# PI2GENESIS-HUB_V20170403.net
KiCad netlist of a schematic drawn in EAGLE
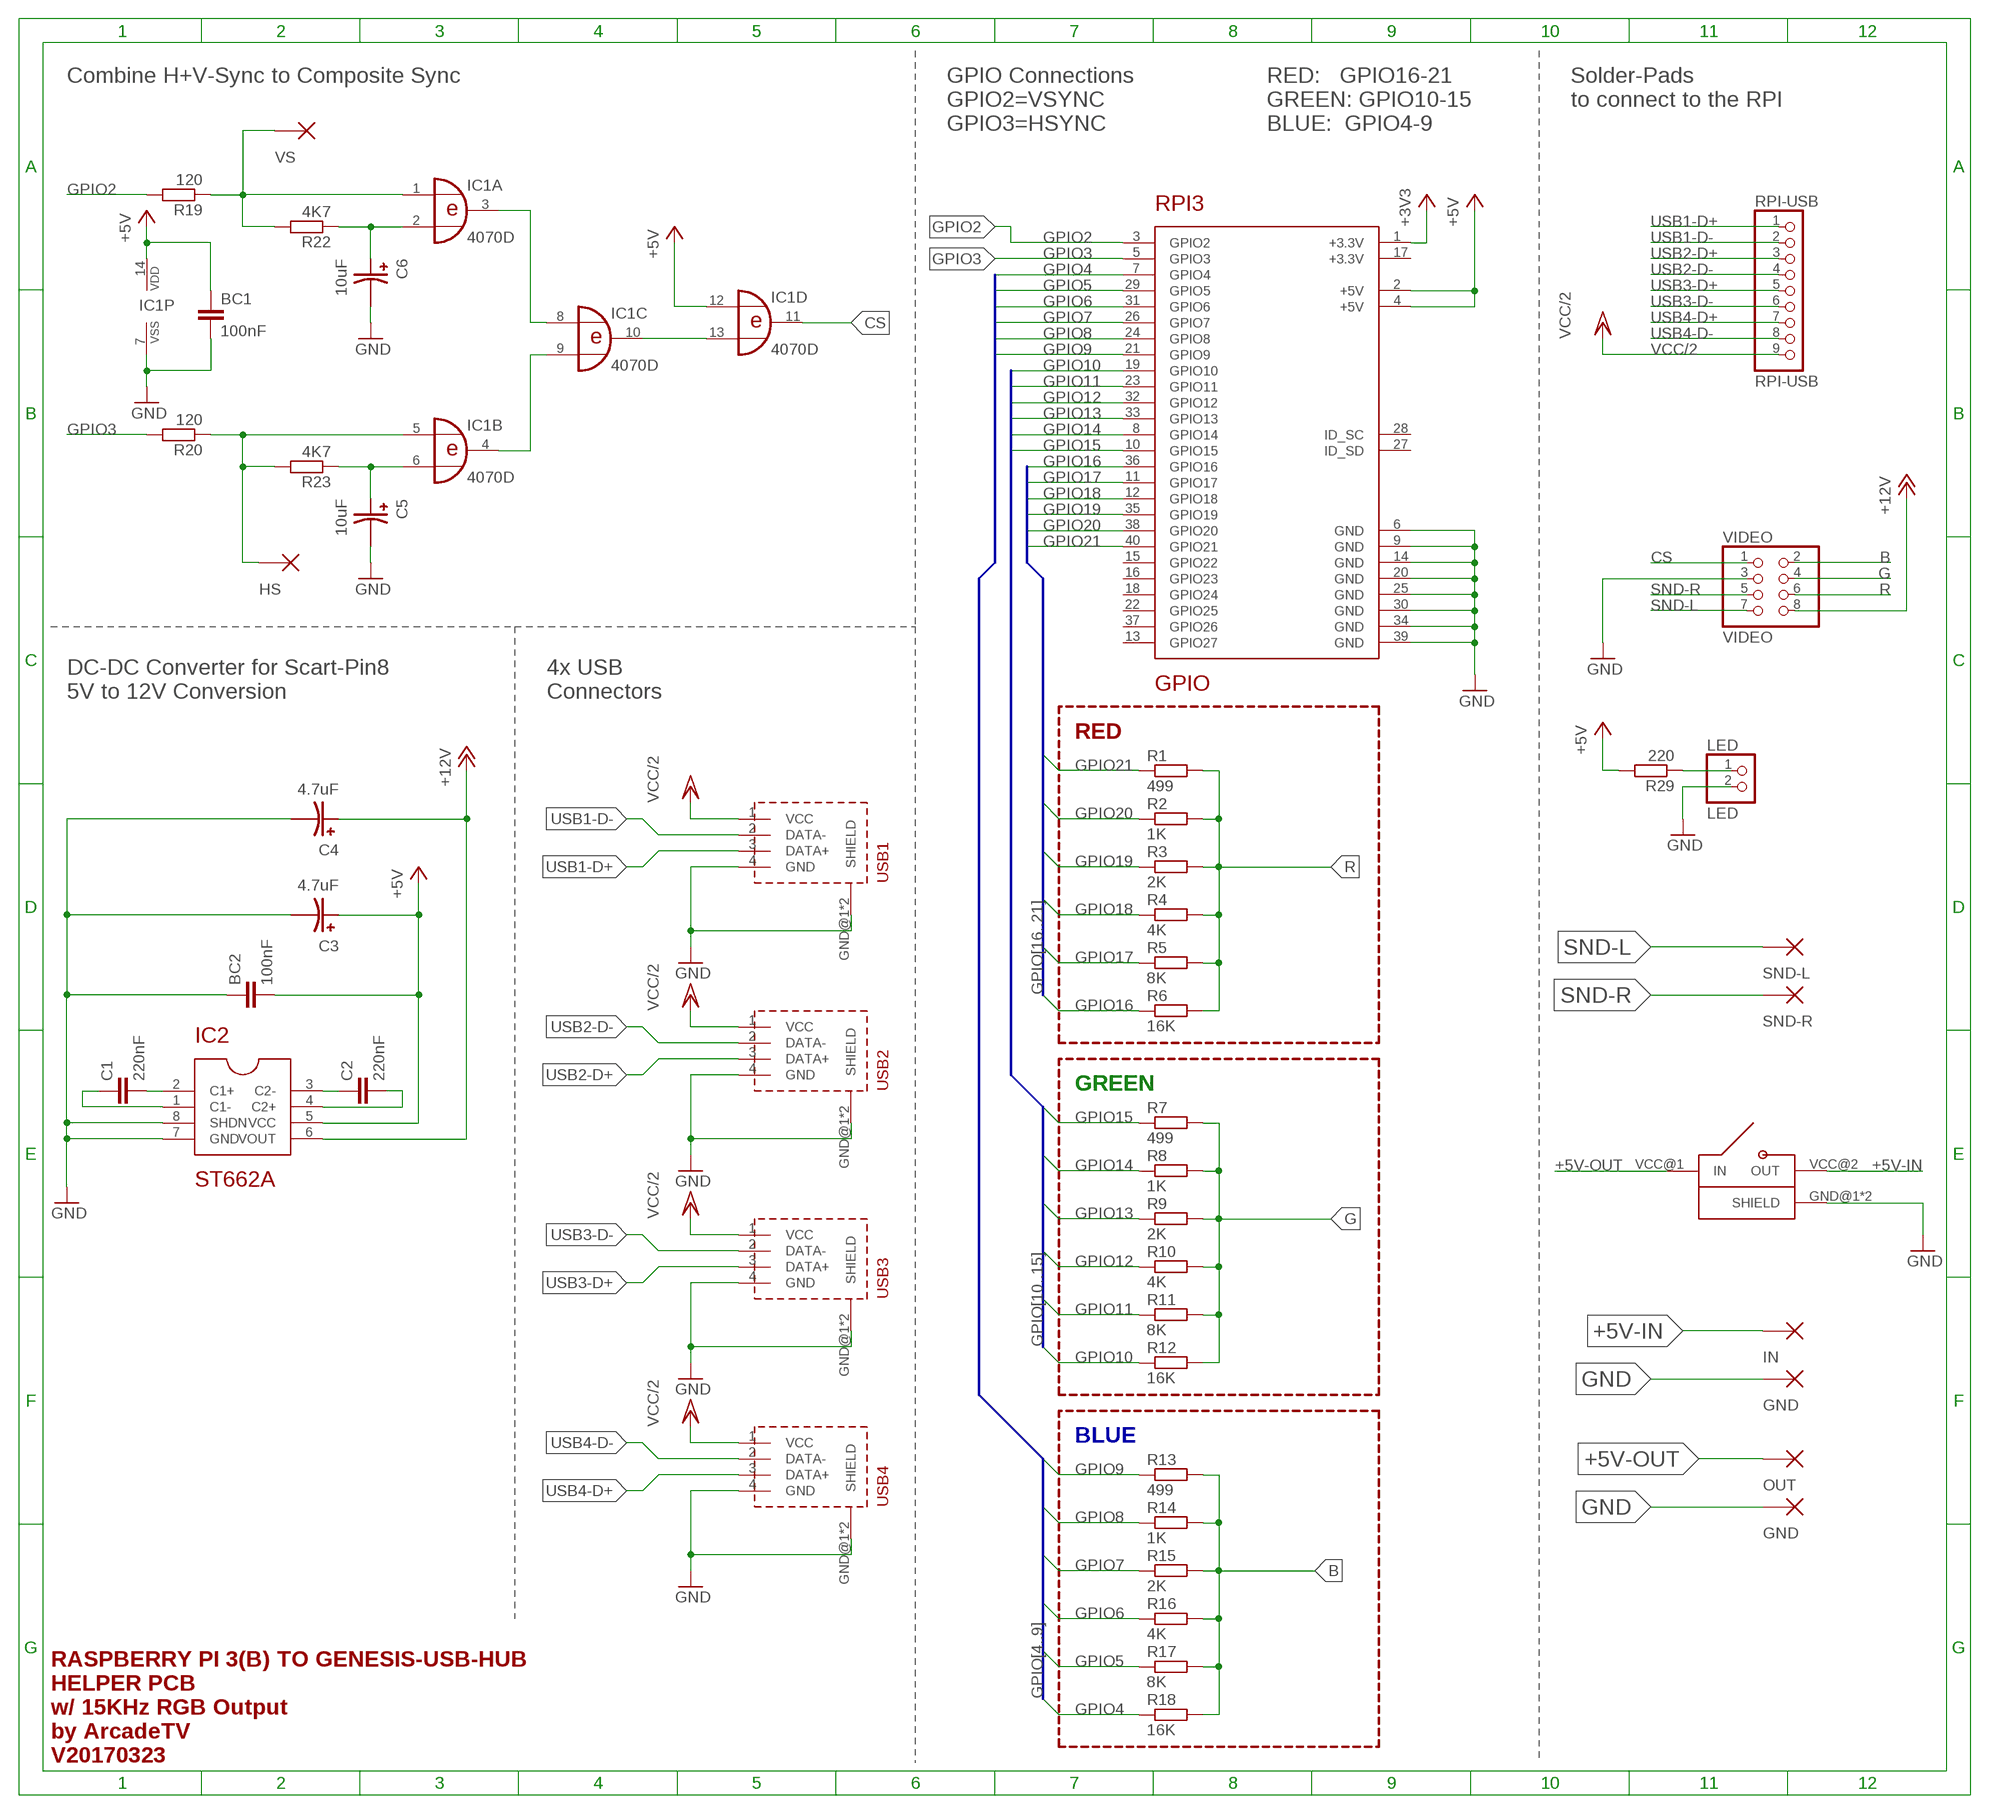
[diagram p0: schematic, sheet 1]

(export (version "E")
  (design (tool "Eeschema 10.0.6"))
  (components
    (comp (ref "BC1")
      (value "100nF")
      (footprint "eagle-import:Z0805")
      (libsource (lib "eagle-import") (part "C0805"))
    )
    (comp (ref "BC2")
      (value "100nF")
      (footprint "eagle-import:Z0805")
      (libsource (lib "eagle-import") (part "C0805"))
    )
    (comp (ref "C1")
      (value "220nF")
      (footprint "eagle-import:Z0805")
      (libsource (lib "eagle-import") (part "C0805"))
    )
    (comp (ref "C2")
      (value "220nF")
      (footprint "eagle-import:Z0805")
      (libsource (lib "eagle-import") (part "C0805"))
    )
    (comp (ref "C3")
      (value "4.7uF")
      (footprint "eagle-import:EEEFPJ101UAR_PANASONIC_VFP-SERIES")
      (libsource (lib "eagle-import") (part "EEEFPJ101UAR_PANASONIC_VFP-SERIES"))
    )
    (comp (ref "C4")
      (value "4.7uF")
      (footprint "eagle-import:EEEFPJ101UAR_PANASONIC_VFP-SERIES")
      (libsource (lib "eagle-import") (part "EEEFPJ101UAR_PANASONIC_VFP-SERIES"))
    )
    (comp (ref "C5")
      (value "10uF")
      (footprint "eagle-import:EEEFPJ101UAR_PANASONIC_VFP-SERIES")
      (libsource (lib "eagle-import") (part "EEEFPJ101UAR_PANASONIC_VFP-SERIES"))
    )
    (comp (ref "C6")
      (value "10uF")
      (footprint "eagle-import:EEEFPJ101UAR_PANASONIC_VFP-SERIES")
      (libsource (lib "eagle-import") (part "EEEFPJ101UAR_PANASONIC_VFP-SERIES"))
    )
    (comp (ref "IC1")
      (value "4070D")
      (footprint "eagle-import:SO14")
      (libsource (lib "eagle-import") (part "4070D"))
    )
    (comp (ref "IC2")
      (value "ST662A")
      (footprint "eagle-import:SO-8")
      (libsource (lib "eagle-import") (part "ST662A"))
    )
    (comp (ref "LED")
      (value "LED")
      (footprint "eagle-import:1X02")
      (libsource (lib "eagle-import") (part "PINHD-1X2"))
    )
    (comp (ref "PAD1")
      (value "HS")
      (footprint "eagle-import:PADS")
      (libsource (lib "eagle-import") (part "PAD"))
    )
    (comp (ref "PAD2")
      (value "VS")
      (footprint "eagle-import:PADS")
      (libsource (lib "eagle-import") (part "PAD"))
    )
    (comp (ref "R1")
      (value "499")
      (footprint "eagle-import:Z0805")
      (libsource (lib "eagle-import") (part "R0805"))
    )
    (comp (ref "R2")
      (value "1K")
      (footprint "eagle-import:Z0805")
      (libsource (lib "eagle-import") (part "R0805"))
    )
    (comp (ref "R3")
      (value "2K")
      (footprint "eagle-import:Z0805")
      (libsource (lib "eagle-import") (part "R0805"))
    )
    (comp (ref "R4")
      (value "4K")
      (footprint "eagle-import:Z0805")
      (libsource (lib "eagle-import") (part "R0805"))
    )
    (comp (ref "R5")
      (value "8K")
      (footprint "eagle-import:Z0805")
      (libsource (lib "eagle-import") (part "R0805"))
    )
    (comp (ref "R6")
      (value "16K")
      (footprint "eagle-import:Z0805")
      (libsource (lib "eagle-import") (part "R0805"))
    )
    (comp (ref "R7")
      (value "499")
      (footprint "eagle-import:Z0805")
      (libsource (lib "eagle-import") (part "R0805"))
    )
    (comp (ref "R8")
      (value "1K")
      (footprint "eagle-import:Z0805")
      (libsource (lib "eagle-import") (part "R0805"))
    )
    (comp (ref "R9")
      (value "2K")
      (footprint "eagle-import:Z0805")
      (libsource (lib "eagle-import") (part "R0805"))
    )
    (comp (ref "R10")
      (value "4K")
      (footprint "eagle-import:Z0805")
      (libsource (lib "eagle-import") (part "R0805"))
    )
    (comp (ref "R11")
      (value "8K")
      (footprint "eagle-import:Z0805")
      (libsource (lib "eagle-import") (part "R0805"))
    )
    (comp (ref "R12")
      (value "16K")
      (footprint "eagle-import:Z0805")
      (libsource (lib "eagle-import") (part "R0805"))
    )
    (comp (ref "R13")
      (value "499")
      (footprint "eagle-import:Z0805")
      (libsource (lib "eagle-import") (part "R0805"))
    )
    (comp (ref "R14")
      (value "1K")
      (footprint "eagle-import:Z0805")
      (libsource (lib "eagle-import") (part "R0805"))
    )
    (comp (ref "R15")
      (value "2K")
      (footprint "eagle-import:Z0805")
      (libsource (lib "eagle-import") (part "R0805"))
    )
    (comp (ref "R16")
      (value "4K")
      (footprint "eagle-import:Z0805")
      (libsource (lib "eagle-import") (part "R0805"))
    )
    (comp (ref "R17")
      (value "8K")
      (footprint "eagle-import:Z0805")
      (libsource (lib "eagle-import") (part "R0805"))
    )
    (comp (ref "R18")
      (value "16K")
      (footprint "eagle-import:Z0805")
      (libsource (lib "eagle-import") (part "R0805"))
    )
    (comp (ref "R19")
      (value "120")
      (footprint "eagle-import:Z0805")
      (libsource (lib "eagle-import") (part "R0805"))
    )
    (comp (ref "R20")
      (value "120")
      (footprint "eagle-import:Z0805")
      (libsource (lib "eagle-import") (part "R0805"))
    )
    (comp (ref "R22")
      (value "4K7")
      (footprint "eagle-import:Z0805")
      (libsource (lib "eagle-import") (part "R0805"))
    )
    (comp (ref "R23")
      (value "4K7")
      (footprint "eagle-import:Z0805")
      (libsource (lib "eagle-import") (part "R0805"))
    )
    (comp (ref "R29")
      (value "220")
      (footprint "eagle-import:Z0805")
      (libsource (lib "eagle-import") (part "R0805"))
    )
    (comp (ref "RPI-USB")
      (value "RPI-USB")
      (footprint "eagle-import:1X09")
      (libsource (lib "eagle-import") (part "PINHD-1X9"))
    )
    (comp (ref "RPI3")
      (value "GPIO")
      (footprint "eagle-import:RPI3-GPIO")
      (libsource (lib "eagle-import") (part "RPI3-GPIOSTANDARD"))
    )
    (comp (ref "U$1")
      (value "OUT")
      (footprint "eagle-import:PADS")
      (libsource (lib "eagle-import") (part "PAD"))
    )
    (comp (ref "U$2")
      (value "SND-L")
      (footprint "eagle-import:PADS")
      (libsource (lib "eagle-import") (part "PAD"))
    )
    (comp (ref "U$3")
      (value "SND-R")
      (footprint "eagle-import:PADS")
      (libsource (lib "eagle-import") (part "PAD"))
    )
    (comp (ref "U$4")
      (value "ALPS-SSSU011700")
      (footprint "eagle-import:ALPS-SSSU011700")
      (libsource (lib "eagle-import") (part "ALPS-SSSU011700"))
    )
    (comp (ref "U$5")
      (value "IN")
      (footprint "eagle-import:PADS")
      (libsource (lib "eagle-import") (part "PAD"))
    )
    (comp (ref "U$6")
      (value "GND")
      (footprint "eagle-import:PADS")
      (libsource (lib "eagle-import") (part "PAD"))
    )
    (comp (ref "U$7")
      (value "GND")
      (footprint "eagle-import:PADS")
      (libsource (lib "eagle-import") (part "PAD"))
    )
    (comp (ref "USB1")
      (value "USB-GENESIS-HUB")
      (footprint "eagle-import:USB-GENESIS-HUB")
      (libsource (lib "eagle-import") (part "USB-GENESIS-HUB"))
    )
    (comp (ref "USB2")
      (value "USB-GENESIS-HUB")
      (footprint "eagle-import:USB-GENESIS-HUB")
      (libsource (lib "eagle-import") (part "USB-GENESIS-HUB"))
    )
    (comp (ref "USB3")
      (value "USB-GENESIS-HUB")
      (footprint "eagle-import:USB-GENESIS-HUB")
      (libsource (lib "eagle-import") (part "USB-GENESIS-HUB"))
    )
    (comp (ref "USB4")
      (value "USB-GENESIS-HUB")
      (footprint "eagle-import:USB-GENESIS-HUB")
      (libsource (lib "eagle-import") (part "USB-GENESIS-HUB"))
    )
    (comp (ref "VIDEO")
      (value "VIDEO")
      (footprint "eagle-import:2X04")
      (libsource (lib "eagle-import") (part "PINHD-2X4"))
    )
  )
  (nets
    (net (code "1") (name "+3V3") (class "Default")
      (node (ref "RPI3") (pin "1") (pinfunction "+3.3V_1") (pintype "bidirectional"))
    )
    (net (code "2") (name "+5V") (class "Default")
      (node (ref "BC1") (pin "1") (pinfunction "1_1") (pintype "passive"))
      (node (ref "BC2") (pin "2") (pinfunction "2_2") (pintype "passive"))
      (node (ref "C3") (pin "PLUS") (pinfunction "+_PLUS") (pintype "bidirectional"))
      (node (ref "IC1") (pin "12") (pinfunction "I0_12") (pintype "input"))
      (node (ref "IC1") (pin "14") (pinfunction "VDD_14") (pintype "power_in"))
      (node (ref "IC2") (pin "5") (pinfunction "VCC_5") (pintype "bidirectional"))
      (node (ref "R29") (pin "2") (pinfunction "2_2") (pintype "passive"))
      (node (ref "RPI3") (pin "2") (pinfunction "+5V_2") (pintype "bidirectional"))
      (node (ref "RPI3") (pin "4") (pinfunction "+5V_4") (pintype "bidirectional"))
    )
    (net (code "3") (name "+5V-IN") (class "Default")
      (node (ref "U$4") (pin "VCC@2") (pinfunction "OUT_VCC@2") (pintype "bidirectional"))
      (node (ref "U$5") (pin "P$1") (pinfunction "P$1_P$1") (pintype "bidirectional"))
    )
    (net (code "4") (name "+5V-OUT") (class "Default")
      (node (ref "U$1") (pin "P$1") (pinfunction "P$1_P$1") (pintype "bidirectional"))
      (node (ref "U$4") (pin "VCC@1") (pinfunction "IN_VCC@1") (pintype "bidirectional"))
    )
    (net (code "5") (name "+12V") (class "Default")
      (node (ref "C4") (pin "PLUS") (pinfunction "+_PLUS") (pintype "bidirectional"))
      (node (ref "IC2") (pin "6") (pinfunction "VOUT_6") (pintype "bidirectional"))
      (node (ref "VIDEO") (pin "8") (pinfunction "8_8") (pintype "passive"))
    )
    (net (code "6") (name "/GPIO4") (class "Default")
      (node (ref "R18") (pin "1") (pinfunction "1_1") (pintype "passive"))
      (node (ref "RPI3") (pin "7") (pinfunction "GPIO4_7") (pintype "bidirectional"))
    )
    (net (code "7") (name "/GPIO5") (class "Default")
      (node (ref "R17") (pin "1") (pinfunction "1_1") (pintype "passive"))
      (node (ref "RPI3") (pin "29") (pinfunction "GPIO5_29") (pintype "bidirectional"))
    )
    (net (code "8") (name "/GPIO6") (class "Default")
      (node (ref "R16") (pin "1") (pinfunction "1_1") (pintype "passive"))
      (node (ref "RPI3") (pin "31") (pinfunction "GPIO6_31") (pintype "bidirectional"))
    )
    (net (code "9") (name "/GPIO7") (class "Default")
      (node (ref "R15") (pin "1") (pinfunction "1_1") (pintype "passive"))
      (node (ref "RPI3") (pin "26") (pinfunction "GPIO7_26") (pintype "bidirectional"))
    )
    (net (code "10") (name "/GPIO8") (class "Default")
      (node (ref "R14") (pin "1") (pinfunction "1_1") (pintype "passive"))
      (node (ref "RPI3") (pin "24") (pinfunction "GPIO8_24") (pintype "bidirectional"))
    )
    (net (code "11") (name "/GPIO9") (class "Default")
      (node (ref "R13") (pin "1") (pinfunction "1_1") (pintype "passive"))
      (node (ref "RPI3") (pin "21") (pinfunction "GPIO9_21") (pintype "bidirectional"))
    )
    (net (code "12") (name "/GPIO10") (class "Default")
      (node (ref "R12") (pin "1") (pinfunction "1_1") (pintype "passive"))
      (node (ref "RPI3") (pin "19") (pinfunction "GPIO10_19") (pintype "bidirectional"))
    )
    (net (code "13") (name "/GPIO11") (class "Default")
      (node (ref "R11") (pin "1") (pinfunction "1_1") (pintype "passive"))
      (node (ref "RPI3") (pin "23") (pinfunction "GPIO11_23") (pintype "bidirectional"))
    )
    (net (code "14") (name "/GPIO12") (class "Default")
      (node (ref "R10") (pin "1") (pinfunction "1_1") (pintype "passive"))
      (node (ref "RPI3") (pin "32") (pinfunction "GPIO12_32") (pintype "bidirectional"))
    )
    (net (code "15") (name "/GPIO13") (class "Default")
      (node (ref "R9") (pin "1") (pinfunction "1_1") (pintype "passive"))
      (node (ref "RPI3") (pin "33") (pinfunction "GPIO13_33") (pintype "bidirectional"))
    )
    (net (code "16") (name "/GPIO14") (class "Default")
      (node (ref "R8") (pin "1") (pinfunction "1_1") (pintype "passive"))
      (node (ref "RPI3") (pin "8") (pinfunction "GPIO14_8") (pintype "bidirectional"))
    )
    (net (code "17") (name "/GPIO15") (class "Default")
      (node (ref "R7") (pin "1") (pinfunction "1_1") (pintype "passive"))
      (node (ref "RPI3") (pin "10") (pinfunction "GPIO15_10") (pintype "bidirectional"))
    )
    (net (code "18") (name "/GPIO16") (class "Default")
      (node (ref "R6") (pin "1") (pinfunction "1_1") (pintype "passive"))
      (node (ref "RPI3") (pin "36") (pinfunction "GPIO16_36") (pintype "bidirectional"))
    )
    (net (code "19") (name "/GPIO17") (class "Default")
      (node (ref "R5") (pin "1") (pinfunction "1_1") (pintype "passive"))
      (node (ref "RPI3") (pin "11") (pinfunction "GPIO17_11") (pintype "bidirectional"))
    )
    (net (code "20") (name "/GPIO18") (class "Default")
      (node (ref "R4") (pin "1") (pinfunction "1_1") (pintype "passive"))
      (node (ref "RPI3") (pin "12") (pinfunction "GPIO18_12") (pintype "bidirectional"))
    )
    (net (code "21") (name "/GPIO19") (class "Default")
      (node (ref "R3") (pin "1") (pinfunction "1_1") (pintype "passive"))
      (node (ref "RPI3") (pin "35") (pinfunction "GPIO19_35") (pintype "bidirectional"))
    )
    (net (code "22") (name "/GPIO20") (class "Default")
      (node (ref "R2") (pin "1") (pinfunction "1_1") (pintype "passive"))
      (node (ref "RPI3") (pin "38") (pinfunction "GPIO20_38") (pintype "bidirectional"))
    )
    (net (code "23") (name "/GPIO21") (class "Default")
      (node (ref "R1") (pin "1") (pinfunction "1_1") (pintype "passive"))
      (node (ref "RPI3") (pin "40") (pinfunction "GPIO21_40") (pintype "bidirectional"))
    )
    (net (code "24") (name "B") (class "Default")
      (node (ref "R13") (pin "2") (pinfunction "2_2") (pintype "passive"))
      (node (ref "R14") (pin "2") (pinfunction "2_2") (pintype "passive"))
      (node (ref "R15") (pin "2") (pinfunction "2_2") (pintype "passive"))
      (node (ref "R16") (pin "2") (pinfunction "2_2") (pintype "passive"))
      (node (ref "R17") (pin "2") (pinfunction "2_2") (pintype "passive"))
      (node (ref "R18") (pin "2") (pinfunction "2_2") (pintype "passive"))
      (node (ref "VIDEO") (pin "2") (pinfunction "2_2") (pintype "passive"))
    )
    (net (code "25") (name "CS") (class "Default")
      (node (ref "IC1") (pin "11") (pinfunction "O_11") (pintype "output"))
      (node (ref "VIDEO") (pin "1") (pinfunction "1_1") (pintype "passive"))
    )
    (net (code "26") (name "G") (class "Default")
      (node (ref "R10") (pin "2") (pinfunction "2_2") (pintype "passive"))
      (node (ref "R11") (pin "2") (pinfunction "2_2") (pintype "passive"))
      (node (ref "R12") (pin "2") (pinfunction "2_2") (pintype "passive"))
      (node (ref "R7") (pin "2") (pinfunction "2_2") (pintype "passive"))
      (node (ref "R8") (pin "2") (pinfunction "2_2") (pintype "passive"))
      (node (ref "R9") (pin "2") (pinfunction "2_2") (pintype "passive"))
      (node (ref "VIDEO") (pin "4") (pinfunction "4_4") (pintype "passive"))
    )
    (net (code "27") (name "GND") (class "Default")
      (node (ref "BC1") (pin "2") (pinfunction "2_2") (pintype "passive"))
      (node (ref "BC2") (pin "1") (pinfunction "1_1") (pintype "passive"))
      (node (ref "C3") (pin "MINUS") (pinfunction "-_MINUS") (pintype "bidirectional"))
      (node (ref "C4") (pin "MINUS") (pinfunction "-_MINUS") (pintype "bidirectional"))
      (node (ref "C5") (pin "MINUS") (pinfunction "-_MINUS") (pintype "bidirectional"))
      (node (ref "C6") (pin "MINUS") (pinfunction "-_MINUS") (pintype "bidirectional"))
      (node (ref "IC1") (pin "7") (pinfunction "VSS_7") (pintype "power_in"))
      (node (ref "IC2") (pin "7") (pinfunction "GND_7") (pintype "bidirectional"))
      (node (ref "IC2") (pin "8") (pinfunction "SHDN_8") (pintype "bidirectional"))
      (node (ref "LED") (pin "2") (pinfunction "2_2") (pintype "passive"))
      (node (ref "RPI3") (pin "14") (pinfunction "GND_14") (pintype "bidirectional"))
      (node (ref "RPI3") (pin "20") (pinfunction "GND_20") (pintype "bidirectional"))
      (node (ref "RPI3") (pin "25") (pinfunction "GND_25") (pintype "bidirectional"))
      (node (ref "RPI3") (pin "30") (pinfunction "GND_30") (pintype "bidirectional"))
      (node (ref "RPI3") (pin "34") (pinfunction "GND_34") (pintype "bidirectional"))
      (node (ref "RPI3") (pin "39") (pinfunction "GND_39") (pintype "bidirectional"))
      (node (ref "RPI3") (pin "6") (pinfunction "GND_6") (pintype "bidirectional"))
      (node (ref "RPI3") (pin "9") (pinfunction "GND_9") (pintype "bidirectional"))
      (node (ref "U$4") (pin "GND@1") (pinfunction "SHIELD_GND@1") (pintype "bidirectional"))
      (node (ref "U$4") (pin "GND@2") (pinfunction "SHIELD_GND@2") (pintype "bidirectional"))
      (node (ref "U$6") (pin "P$1") (pinfunction "P$1_P$1") (pintype "bidirectional"))
      (node (ref "U$7") (pin "P$1") (pinfunction "P$1_P$1") (pintype "bidirectional"))
      (node (ref "USB1") (pin "4") (pinfunction "GND_4") (pintype "bidirectional"))
      (node (ref "USB1") (pin "GND@1") (pinfunction "SHIELD_GND@1") (pintype "bidirectional"))
      (node (ref "USB1") (pin "GND@2") (pinfunction "SHIELD_GND@2") (pintype "bidirectional"))
      (node (ref "USB2") (pin "4") (pinfunction "GND_4") (pintype "bidirectional"))
      (node (ref "USB2") (pin "GND@1") (pinfunction "SHIELD_GND@1") (pintype "bidirectional"))
      (node (ref "USB2") (pin "GND@2") (pinfunction "SHIELD_GND@2") (pintype "bidirectional"))
      (node (ref "USB3") (pin "4") (pinfunction "GND_4") (pintype "bidirectional"))
      (node (ref "USB3") (pin "GND@1") (pinfunction "SHIELD_GND@1") (pintype "bidirectional"))
      (node (ref "USB3") (pin "GND@2") (pinfunction "SHIELD_GND@2") (pintype "bidirectional"))
      (node (ref "USB4") (pin "4") (pinfunction "GND_4") (pintype "bidirectional"))
      (node (ref "USB4") (pin "GND@1") (pinfunction "SHIELD_GND@1") (pintype "bidirectional"))
      (node (ref "USB4") (pin "GND@2") (pinfunction "SHIELD_GND@2") (pintype "bidirectional"))
      (node (ref "VIDEO") (pin "3") (pinfunction "3_3") (pintype "passive"))
    )
    (net (code "28") (name "GPIO2") (class "Default")
      (node (ref "R19") (pin "2") (pinfunction "2_2") (pintype "passive"))
      (node (ref "RPI3") (pin "3") (pinfunction "GPIO2_3") (pintype "bidirectional"))
    )
    (net (code "29") (name "GPIO3") (class "Default")
      (node (ref "R20") (pin "2") (pinfunction "2_2") (pintype "passive"))
      (node (ref "RPI3") (pin "5") (pinfunction "GPIO3_5") (pintype "bidirectional"))
    )
    (net (code "30") (name "Net-(C5-+)") (class "Default")
      (node (ref "C5") (pin "PLUS") (pinfunction "+_PLUS") (pintype "bidirectional"))
      (node (ref "IC1") (pin "6") (pinfunction "I1_6") (pintype "input"))
      (node (ref "R23") (pin "1") (pinfunction "1_1") (pintype "passive"))
    )
    (net (code "31") (name "Net-(C6-+)") (class "Default")
      (node (ref "C6") (pin "PLUS") (pinfunction "+_PLUS") (pintype "bidirectional"))
      (node (ref "IC1") (pin "2") (pinfunction "I1_2") (pintype "input"))
      (node (ref "R22") (pin "1") (pinfunction "1_1") (pintype "passive"))
    )
    (net (code "32") (name "Net-(IC1A-I0)") (class "Default")
      (node (ref "IC1") (pin "1") (pinfunction "I0_1") (pintype "input"))
      (node (ref "PAD2") (pin "P$1") (pinfunction "P$1_P$1") (pintype "bidirectional"))
      (node (ref "R19") (pin "1") (pinfunction "1_1") (pintype "passive"))
      (node (ref "R22") (pin "2") (pinfunction "2_2") (pintype "passive"))
    )
    (net (code "33") (name "Net-(IC1A-O)") (class "Default")
      (node (ref "IC1") (pin "3") (pinfunction "O_3") (pintype "output"))
      (node (ref "IC1") (pin "8") (pinfunction "I0_8") (pintype "input"))
    )
    (net (code "34") (name "Net-(IC1B-I0)") (class "Default")
      (node (ref "IC1") (pin "5") (pinfunction "I0_5") (pintype "input"))
      (node (ref "PAD1") (pin "P$1") (pinfunction "P$1_P$1") (pintype "bidirectional"))
      (node (ref "R20") (pin "1") (pinfunction "1_1") (pintype "passive"))
      (node (ref "R23") (pin "2") (pinfunction "2_2") (pintype "passive"))
    )
    (net (code "35") (name "Net-(IC1B-O)") (class "Default")
      (node (ref "IC1") (pin "4") (pinfunction "O_4") (pintype "output"))
      (node (ref "IC1") (pin "9") (pinfunction "I1_9") (pintype "input"))
    )
    (net (code "36") (name "Net-(IC1C-O)") (class "Default")
      (node (ref "IC1") (pin "10") (pinfunction "O_10") (pintype "output"))
      (node (ref "IC1") (pin "13") (pinfunction "I1_13") (pintype "input"))
    )
    (net (code "37") (name "Net-(IC2-C1+)") (class "Default")
      (node (ref "C1") (pin "2") (pinfunction "2_2") (pintype "passive"))
      (node (ref "IC2") (pin "2") (pinfunction "C1+_2") (pintype "bidirectional"))
    )
    (net (code "38") (name "Net-(IC2-C1-)") (class "Default")
      (node (ref "C1") (pin "1") (pinfunction "1_1") (pintype "passive"))
      (node (ref "IC2") (pin "1") (pinfunction "C1-_1") (pintype "bidirectional"))
    )
    (net (code "39") (name "Net-(IC2-C2+)") (class "Default")
      (node (ref "C2") (pin "2") (pinfunction "2_2") (pintype "passive"))
      (node (ref "IC2") (pin "4") (pinfunction "C2+_4") (pintype "bidirectional"))
    )
    (net (code "40") (name "Net-(IC2-C2-)") (class "Default")
      (node (ref "C2") (pin "1") (pinfunction "1_1") (pintype "passive"))
      (node (ref "IC2") (pin "3") (pinfunction "C2-_3") (pintype "bidirectional"))
    )
    (net (code "41") (name "Net-(LED-Pad1)") (class "Default")
      (node (ref "LED") (pin "1") (pinfunction "1_1") (pintype "passive"))
      (node (ref "R29") (pin "1") (pinfunction "1_1") (pintype "passive"))
    )
    (net (code "42") (name "R") (class "Default")
      (node (ref "R1") (pin "2") (pinfunction "2_2") (pintype "passive"))
      (node (ref "R2") (pin "2") (pinfunction "2_2") (pintype "passive"))
      (node (ref "R3") (pin "2") (pinfunction "2_2") (pintype "passive"))
      (node (ref "R4") (pin "2") (pinfunction "2_2") (pintype "passive"))
      (node (ref "R5") (pin "2") (pinfunction "2_2") (pintype "passive"))
      (node (ref "R6") (pin "2") (pinfunction "2_2") (pintype "passive"))
      (node (ref "VIDEO") (pin "6") (pinfunction "6_6") (pintype "passive"))
    )
    (net (code "43") (name "SND-L") (class "Default")
      (node (ref "U$2") (pin "P$1") (pinfunction "P$1_P$1") (pintype "bidirectional"))
      (node (ref "VIDEO") (pin "7") (pinfunction "7_7") (pintype "passive"))
    )
    (net (code "44") (name "SND-R") (class "Default")
      (node (ref "U$3") (pin "P$1") (pinfunction "P$1_P$1") (pintype "bidirectional"))
      (node (ref "VIDEO") (pin "5") (pinfunction "5_5") (pintype "passive"))
    )
    (net (code "45") (name "USB1-D+") (class "Default")
      (node (ref "RPI-USB") (pin "1") (pinfunction "1_1") (pintype "passive"))
      (node (ref "USB1") (pin "3") (pinfunction "DATA+_3") (pintype "bidirectional"))
    )
    (net (code "46") (name "USB1-D-") (class "Default")
      (node (ref "RPI-USB") (pin "2") (pinfunction "2_2") (pintype "passive"))
      (node (ref "USB1") (pin "2") (pinfunction "DATA-_2") (pintype "bidirectional"))
    )
    (net (code "47") (name "USB2-D+") (class "Default")
      (node (ref "RPI-USB") (pin "3") (pinfunction "3_3") (pintype "passive"))
      (node (ref "USB2") (pin "3") (pinfunction "DATA+_3") (pintype "bidirectional"))
    )
    (net (code "48") (name "USB2-D-") (class "Default")
      (node (ref "RPI-USB") (pin "4") (pinfunction "4_4") (pintype "passive"))
      (node (ref "USB2") (pin "2") (pinfunction "DATA-_2") (pintype "bidirectional"))
    )
    (net (code "49") (name "USB3-D+") (class "Default")
      (node (ref "RPI-USB") (pin "5") (pinfunction "5_5") (pintype "passive"))
      (node (ref "USB3") (pin "3") (pinfunction "DATA+_3") (pintype "bidirectional"))
    )
    (net (code "50") (name "USB3-D-") (class "Default")
      (node (ref "RPI-USB") (pin "6") (pinfunction "6_6") (pintype "passive"))
      (node (ref "USB3") (pin "2") (pinfunction "DATA-_2") (pintype "bidirectional"))
    )
    (net (code "51") (name "USB4-D+") (class "Default")
      (node (ref "RPI-USB") (pin "7") (pinfunction "7_7") (pintype "passive"))
      (node (ref "USB4") (pin "3") (pinfunction "DATA+_3") (pintype "bidirectional"))
    )
    (net (code "52") (name "USB4-D-") (class "Default")
      (node (ref "RPI-USB") (pin "8") (pinfunction "8_8") (pintype "passive"))
      (node (ref "USB4") (pin "2") (pinfunction "DATA-_2") (pintype "bidirectional"))
    )
    (net (code "53") (name "VCC{slash}2") (class "Default")
      (node (ref "RPI-USB") (pin "9") (pinfunction "9_9") (pintype "passive"))
      (node (ref "USB1") (pin "1") (pinfunction "VCC_1") (pintype "bidirectional"))
      (node (ref "USB2") (pin "1") (pinfunction "VCC_1") (pintype "bidirectional"))
      (node (ref "USB3") (pin "1") (pinfunction "VCC_1") (pintype "bidirectional"))
      (node (ref "USB4") (pin "1") (pinfunction "VCC_1") (pintype "bidirectional"))
    )
    (net (code "54") (name "unconnected-(RPI3-+3.3V-Pad17)") (class "Default")
      (node (ref "RPI3") (pin "17") (pinfunction "+3.3V_17") (pintype "bidirectional"))
    )
    (net (code "55") (name "unconnected-(RPI3-GPIO22-Pad15)") (class "Default")
      (node (ref "RPI3") (pin "15") (pinfunction "GPIO22_15") (pintype "bidirectional"))
    )
    (net (code "56") (name "unconnected-(RPI3-GPIO23-Pad16)") (class "Default")
      (node (ref "RPI3") (pin "16") (pinfunction "GPIO23_16") (pintype "bidirectional"))
    )
    (net (code "57") (name "unconnected-(RPI3-GPIO24-Pad18)") (class "Default")
      (node (ref "RPI3") (pin "18") (pinfunction "GPIO24_18") (pintype "bidirectional"))
    )
    (net (code "58") (name "unconnected-(RPI3-GPIO25-Pad22)") (class "Default")
      (node (ref "RPI3") (pin "22") (pinfunction "GPIO25_22") (pintype "bidirectional"))
    )
    (net (code "59") (name "unconnected-(RPI3-GPIO26-Pad37)") (class "Default")
      (node (ref "RPI3") (pin "37") (pinfunction "GPIO26_37") (pintype "bidirectional"))
    )
    (net (code "60") (name "unconnected-(RPI3-GPIO27-Pad13)") (class "Default")
      (node (ref "RPI3") (pin "13") (pinfunction "GPIO27_13") (pintype "bidirectional"))
    )
    (net (code "61") (name "unconnected-(RPI3-ID_SC-Pad28)") (class "Default")
      (node (ref "RPI3") (pin "28") (pinfunction "ID_SC_28") (pintype "bidirectional"))
    )
    (net (code "62") (name "unconnected-(RPI3-ID_SD-Pad27)") (class "Default")
      (node (ref "RPI3") (pin "27") (pinfunction "ID_SD_27") (pintype "bidirectional"))
    )
  )
)
